# CP_Solenoid3.net
KiCad netlist of a schematic drawn in EAGLE
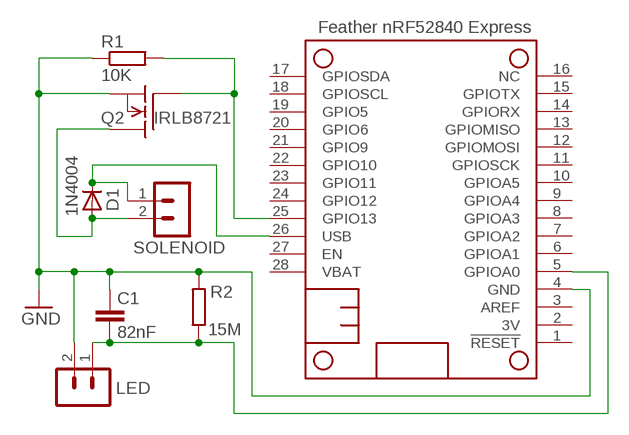
[diagram p0: schematic, sheet 1]

(export (version "E")
  (design (tool "Eeschema 10.0.6"))
  (components
    (comp (ref "C1")
      (value "82nF")
      (footprint "eagle-import:C025-025X050")
      (libsource (lib "eagle-import") (part "C-EU025-025X050"))
    )
    (comp (ref "D1")
      (value "1N4004")
      (footprint "eagle-import:DO41-10")
      (libsource (lib "eagle-import") (part "1N4004"))
    )
    (comp (ref "LED")
      (value "B2B-PH-K-S")
      (footprint "eagle-import:B2B-PH-K-S")
      (libsource (lib "eagle-import") (part "B2B-PH-K-S"))
    )
    (comp (ref "MS1")
      (value "FEATHERWING_NODIM")
      (footprint "eagle-import:FEATHERWING_DIM")
      (libsource (lib "eagle-import") (part "FEATHERWING_NODIM"))
    )
    (comp (ref "Q2")
      (value "IRLB8721")
      (footprint "eagle-import:TO220")
      (libsource (lib "eagle-import") (part "IRF510"))
    )
    (comp (ref "R1")
      (value "10K")
      (footprint "eagle-import:0207_10")
      (libsource (lib "eagle-import") (part "R-EU_0207/10"))
    )
    (comp (ref "R2")
      (value "15M")
      (footprint "eagle-import:0414_15")
      (libsource (lib "eagle-import") (part "R-EU_0414/15"))
    )
    (comp (ref "SOLENOID")
      (value "B2B-PH-K-S")
      (footprint "eagle-import:B2B-PH-K-S")
      (libsource (lib "eagle-import") (part "B2B-PH-K-S"))
    )
  )
  (nets
    (net (code "1") (name "/3V") (class "Default")
      (node (ref "MS1") (pin "2") (pinfunction "3V_2") (pintype "power_in"))
    )
    (net (code "2") (name "/VBAT") (class "Default")
      (node (ref "MS1") (pin "28") (pinfunction "VBAT_28") (pintype "power_in"))
    )
    (net (code "3") (name "GND") (class "Default")
      (node (ref "C1") (pin "1") (pinfunction "1_1") (pintype "passive"))
      (node (ref "LED") (pin "2") (pinfunction "2_2") (pintype "passive"))
      (node (ref "MS1") (pin "4") (pinfunction "GND_4") (pintype "power_in"))
      (node (ref "Q2") (pin "3") (pinfunction "S_3") (pintype "passive"))
      (node (ref "R1") (pin "1") (pinfunction "1_1") (pintype "passive"))
      (node (ref "R2") (pin "2") (pinfunction "2_2") (pintype "passive"))
    )
    (net (code "4") (name "Net-(MS1-GPIO13)") (class "Default")
      (node (ref "MS1") (pin "25") (pinfunction "GPIO13_25") (pintype "bidirectional"))
      (node (ref "Q2") (pin "1") (pinfunction "G_1") (pintype "passive"))
      (node (ref "R1") (pin "2") (pinfunction "2_2") (pintype "passive"))
    )
    (net (code "5") (name "Net-(MS1-GPIOA0)") (class "Default")
      (node (ref "C1") (pin "2") (pinfunction "2_2") (pintype "passive"))
      (node (ref "LED") (pin "1") (pinfunction "1_1") (pintype "passive"))
      (node (ref "MS1") (pin "5") (pinfunction "GPIOA0_5") (pintype "bidirectional"))
      (node (ref "R2") (pin "1") (pinfunction "1_1") (pintype "passive"))
    )
    (net (code "6") (name "Net-(MS1-USB)") (class "Default")
      (node (ref "D1") (pin "C") (pinfunction "C_C") (pintype "passive"))
      (node (ref "MS1") (pin "26") (pinfunction "USB_26") (pintype "power_in"))
      (node (ref "SOLENOID") (pin "1") (pinfunction "1_1") (pintype "passive"))
    )
    (net (code "7") (name "Net-(Q2-D)") (class "Default")
      (node (ref "D1") (pin "A") (pinfunction "A_A") (pintype "passive"))
      (node (ref "Q2") (pin "2") (pinfunction "D_2") (pintype "passive"))
      (node (ref "SOLENOID") (pin "2") (pinfunction "2_2") (pintype "passive"))
    )
    (net (code "8") (name "unconnected-(MS1-AREF-Pad3)") (class "Default")
      (node (ref "MS1") (pin "3") (pinfunction "AREF_3") (pintype "passive"))
    )
    (net (code "9") (name "unconnected-(MS1-EN-Pad27)") (class "Default")
      (node (ref "MS1") (pin "27") (pinfunction "EN_27") (pintype "passive"))
    )
    (net (code "10") (name "unconnected-(MS1-GPIO5-Pad19)") (class "Default")
      (node (ref "MS1") (pin "19") (pinfunction "GPIO5_19") (pintype "bidirectional"))
    )
    (net (code "11") (name "unconnected-(MS1-GPIO6-Pad20)") (class "Default")
      (node (ref "MS1") (pin "20") (pinfunction "GPIO6_20") (pintype "bidirectional"))
    )
    (net (code "12") (name "unconnected-(MS1-GPIO9-Pad21)") (class "Default")
      (node (ref "MS1") (pin "21") (pinfunction "GPIO9_21") (pintype "bidirectional"))
    )
    (net (code "13") (name "unconnected-(MS1-GPIO10-Pad22)") (class "Default")
      (node (ref "MS1") (pin "22") (pinfunction "GPIO10_22") (pintype "bidirectional"))
    )
    (net (code "14") (name "unconnected-(MS1-GPIO11-Pad23)") (class "Default")
      (node (ref "MS1") (pin "23") (pinfunction "GPIO11_23") (pintype "bidirectional"))
    )
    (net (code "15") (name "unconnected-(MS1-GPIO12-Pad24)") (class "Default")
      (node (ref "MS1") (pin "24") (pinfunction "GPIO12_24") (pintype "bidirectional"))
    )
    (net (code "16") (name "unconnected-(MS1-GPIOA1-Pad6)") (class "Default")
      (node (ref "MS1") (pin "6") (pinfunction "GPIOA1_6") (pintype "bidirectional"))
    )
    (net (code "17") (name "unconnected-(MS1-GPIOA2-Pad7)") (class "Default")
      (node (ref "MS1") (pin "7") (pinfunction "GPIOA2_7") (pintype "bidirectional"))
    )
    (net (code "18") (name "unconnected-(MS1-GPIOA3-Pad8)") (class "Default")
      (node (ref "MS1") (pin "8") (pinfunction "GPIOA3_8") (pintype "bidirectional"))
    )
    (net (code "19") (name "unconnected-(MS1-GPIOA4-Pad9)") (class "Default")
      (node (ref "MS1") (pin "9") (pinfunction "GPIOA4_9") (pintype "bidirectional"))
    )
    (net (code "20") (name "unconnected-(MS1-GPIOA5-Pad10)") (class "Default")
      (node (ref "MS1") (pin "10") (pinfunction "GPIOA5_10") (pintype "bidirectional"))
    )
    (net (code "21") (name "unconnected-(MS1-GPIOMISO-Pad13)") (class "Default")
      (node (ref "MS1") (pin "13") (pinfunction "GPIOMISO_13") (pintype "bidirectional"))
    )
    (net (code "22") (name "unconnected-(MS1-GPIOMOSI-Pad12)") (class "Default")
      (node (ref "MS1") (pin "12") (pinfunction "GPIOMOSI_12") (pintype "bidirectional"))
    )
    (net (code "23") (name "unconnected-(MS1-GPIORX-Pad14)") (class "Default")
      (node (ref "MS1") (pin "14") (pinfunction "GPIORX_14") (pintype "bidirectional"))
    )
    (net (code "24") (name "unconnected-(MS1-GPIOSCK-Pad11)") (class "Default")
      (node (ref "MS1") (pin "11") (pinfunction "GPIOSCK_11") (pintype "bidirectional"))
    )
    (net (code "25") (name "unconnected-(MS1-GPIOSCL-Pad18)") (class "Default")
      (node (ref "MS1") (pin "18") (pinfunction "GPIOSCL_18") (pintype "bidirectional"))
    )
    (net (code "26") (name "unconnected-(MS1-GPIOSDA-Pad17)") (class "Default")
      (node (ref "MS1") (pin "17") (pinfunction "GPIOSDA_17") (pintype "bidirectional"))
    )
    (net (code "27") (name "unconnected-(MS1-GPIOTX-Pad15)") (class "Default")
      (node (ref "MS1") (pin "15") (pinfunction "GPIOTX_15") (pintype "bidirectional"))
    )
    (net (code "28") (name "unconnected-(MS1-NC-Pad16)") (class "Default")
      (node (ref "MS1") (pin "16") (pinfunction "NC_16") (pintype "passive"))
    )
    (net (code "29") (name "unconnected-(MS1-~{RESET}-Pad1)") (class "Default")
      (node (ref "MS1") (pin "1") (pinfunction "~{RESET}_1") (pintype "input"))
    )
  )
)
